# SCH_Arduino__V1_2023-10-04.net
KiCad netlist of a schematic drawn in EasyEDA
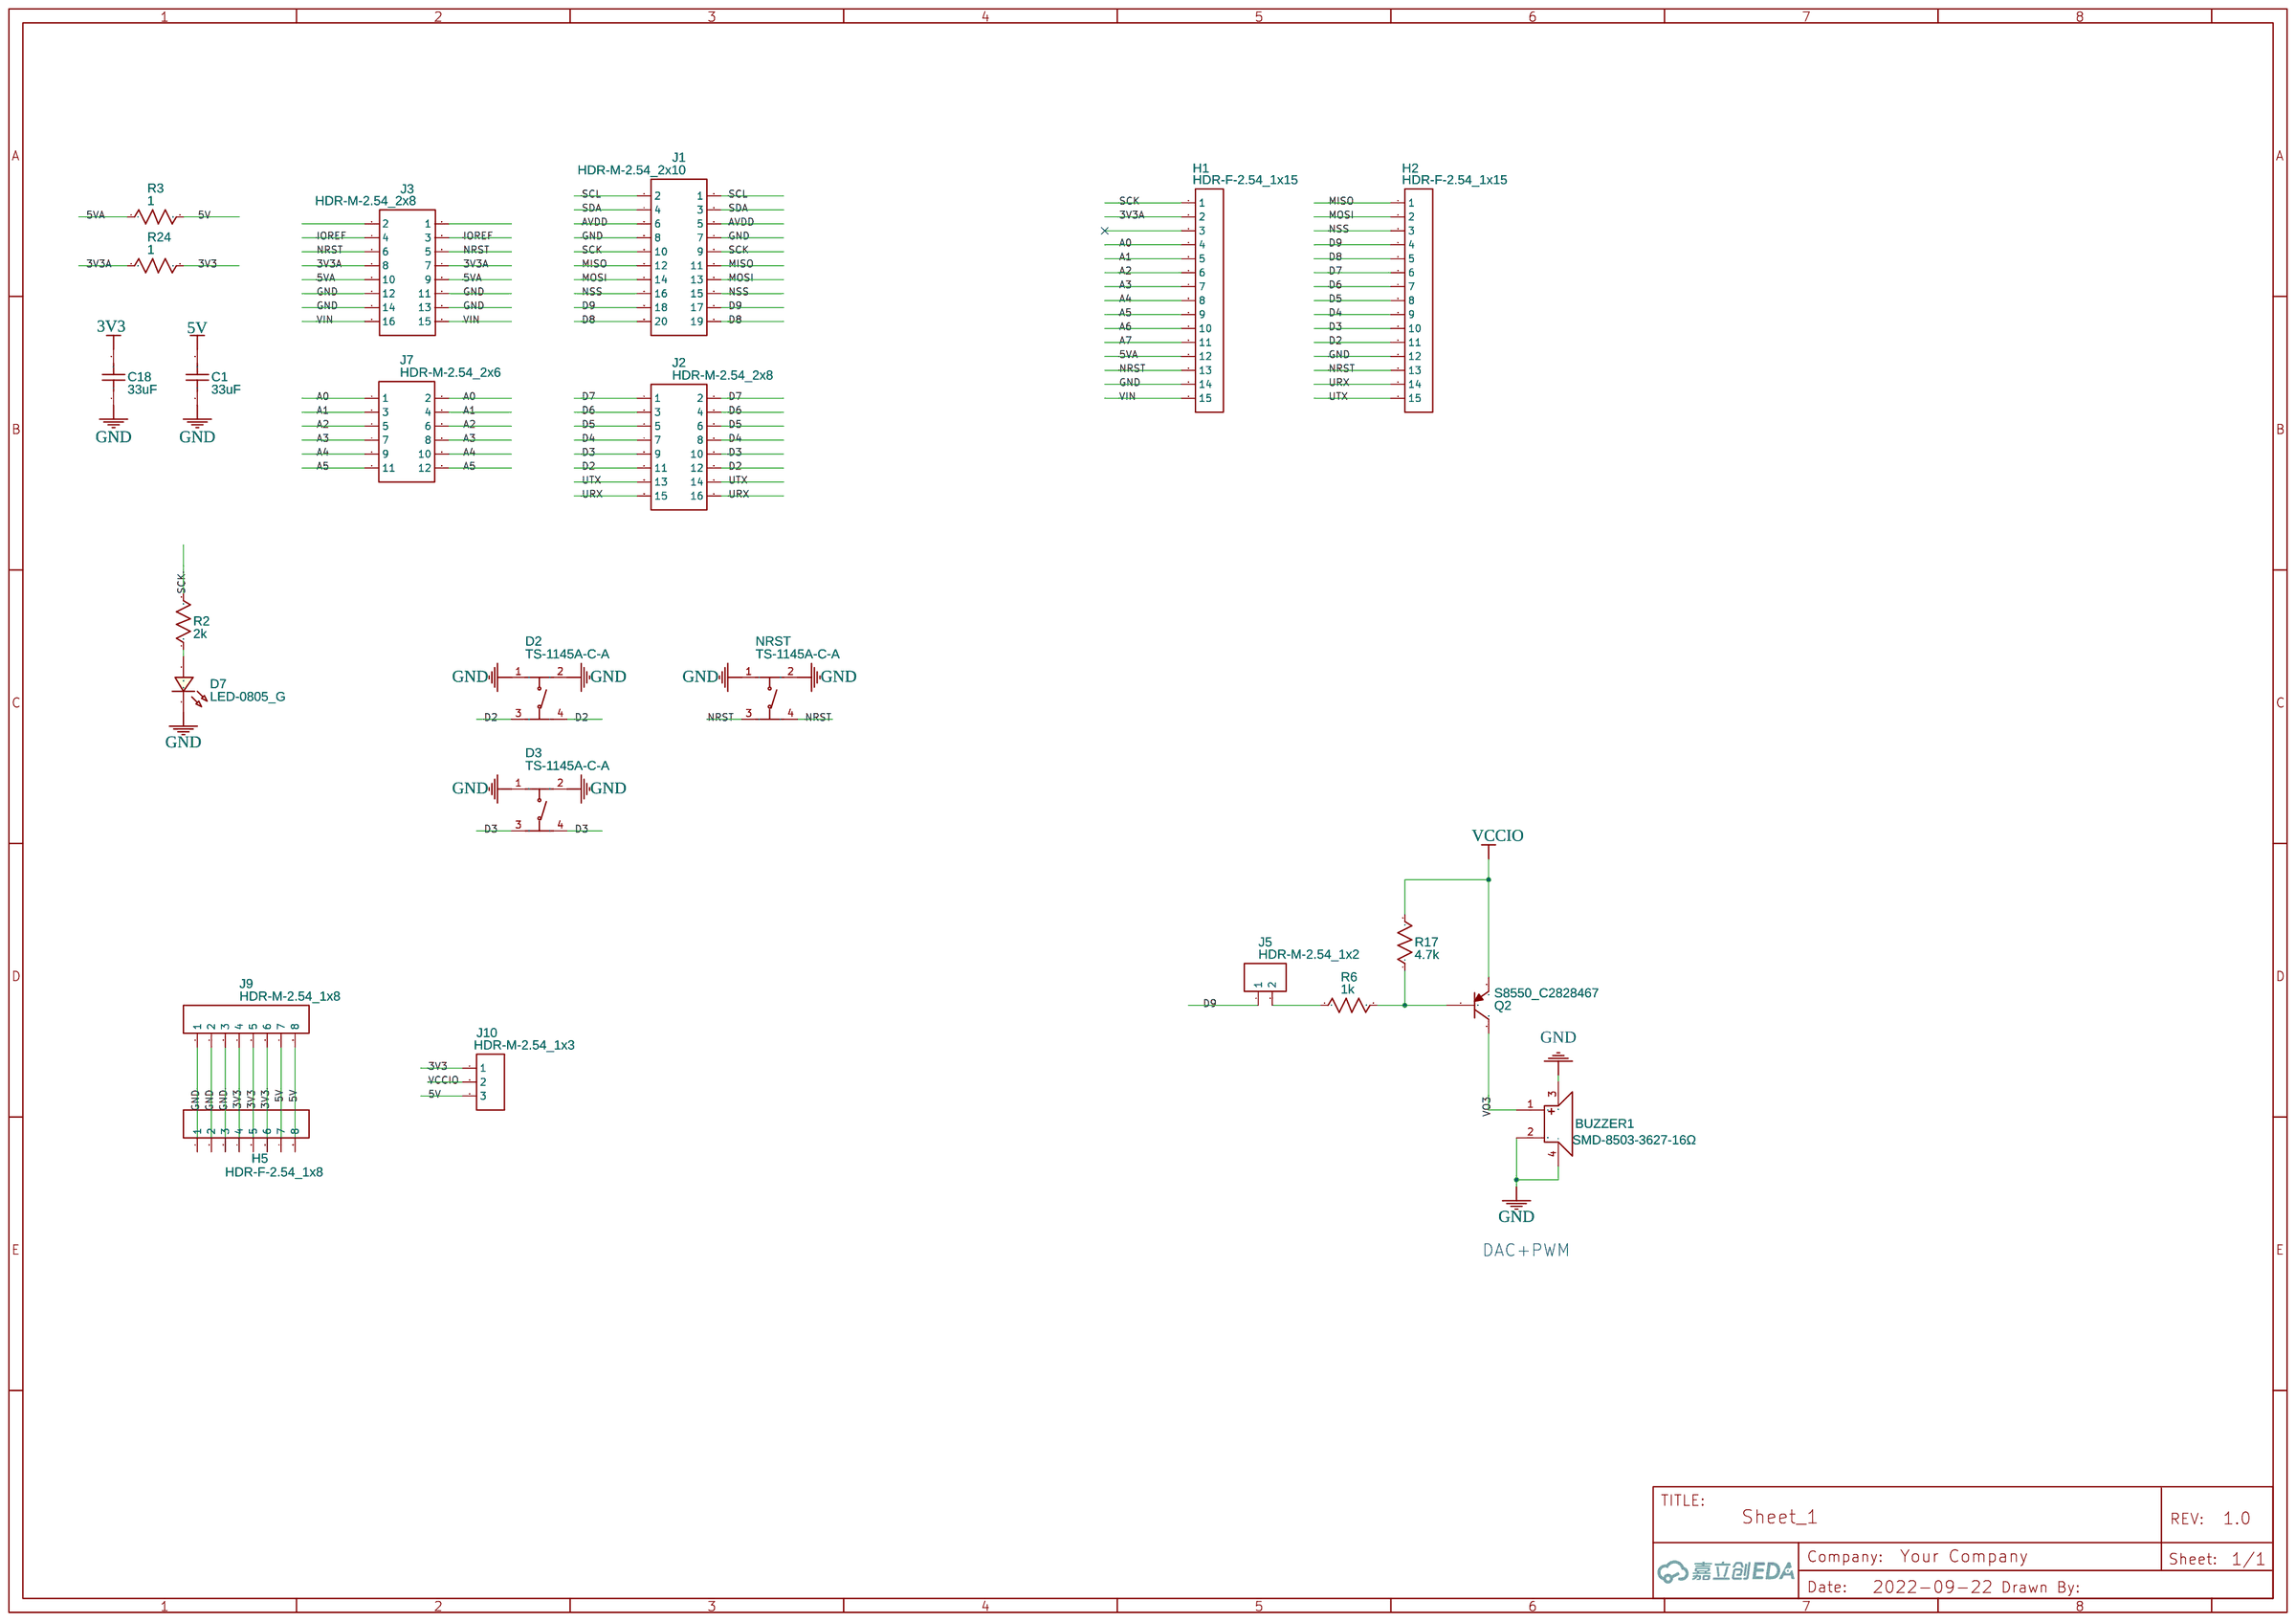
[diagram p0: 连接器]
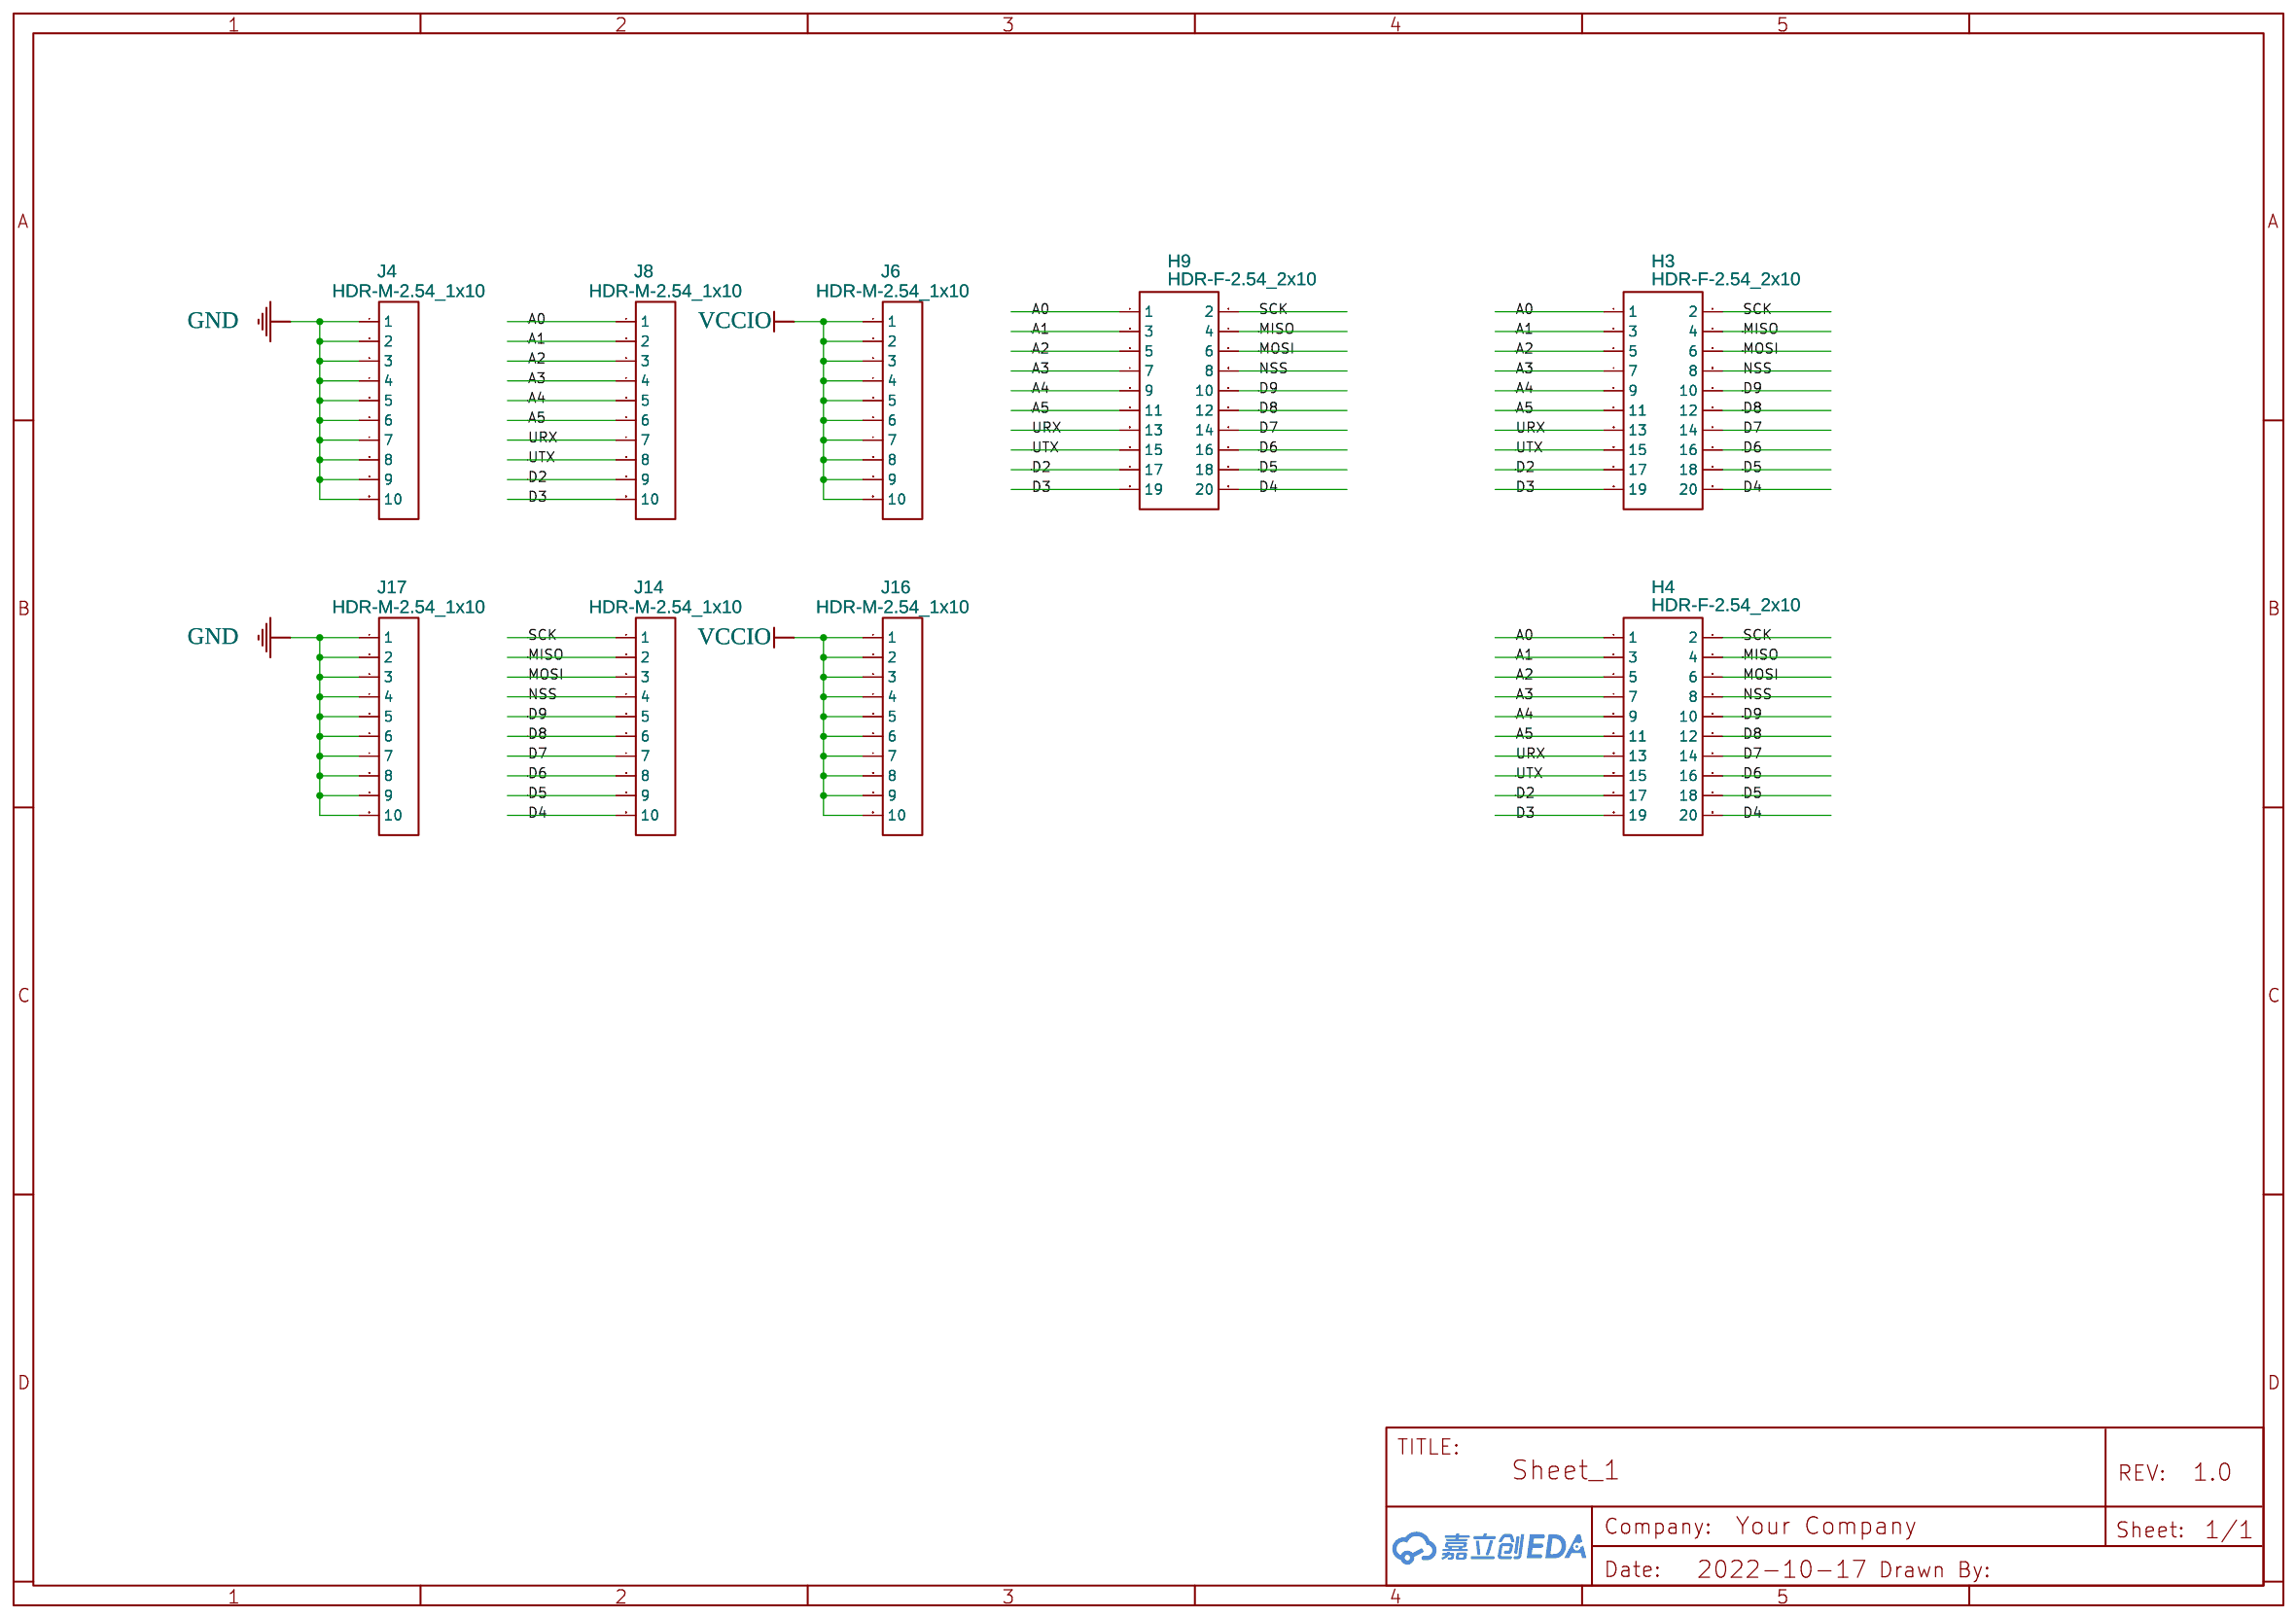
[diagram p1: 连接器扩展]

(export (version "E")
  (design (tool "Eeschema 10.0.6"))
  (components
    (comp (ref "BUZZER1")
      (value "SMD-8503-3627-16Ω")
      (fields (field (name "BOM_Supplier Part") "C2685545"))
      (libsource (lib "") (part "SMD-8503-3627-16Ω"))
    )
    (comp (ref "C1")
      (value "33uF")
      (fields
        (field (name "BOM_Manufacturer Part") "C3225X5R0J336MT0A0N")
        (field (name "BOM_Supplier Part") "C695362")
      )
      (libsource (lib "") (part "C3225X5R0J336MT0A0N"))
    )
    (comp (ref "C18")
      (value "33uF")
      (fields
        (field (name "BOM_Manufacturer Part") "C3225X5R0J336MT0A0N")
        (field (name "BOM_Supplier Part") "C695362")
      )
      (libsource (lib "") (part "C3225X5R0J336MT0A0N"))
    )
    (comp (ref "D2")
      (value "TS-1145A-C-A")
      (fields (field (name "BOM_Supplier Part") "C318903"))
      (libsource (lib "") (part "TS-1145A-C-A_1"))
    )
    (comp (ref "D3")
      (value "TS-1145A-C-A")
      (fields (field (name "BOM_Supplier Part") "C318903"))
      (libsource (lib "") (part "TS-1145A-C-A_1"))
    )
    (comp (ref "D7")
      (value "LED-0805_G")
      (fields (field (name "BOM_Manufacturer Part") "NCD0805G1") (field (name "BOM_Supplier Part") "C84260"))
      (libsource (lib "") (part "LED-0805_G"))
    )
    (comp (ref "H1")
      (value "HDR-F-2.54_1x15")
      (fields (field (name "BOM_Supplier Part") "C124408"))
      (libsource (lib "") (part "HDR-F-2.54_1x15"))
    )
    (comp (ref "H2")
      (value "HDR-F-2.54_1x15")
      (fields (field (name "BOM_Supplier Part") "C124408"))
      (libsource (lib "") (part "HDR-F-2.54_1x15"))
    )
    (comp (ref "H5")
      (value "HDR-F-2.54_1x8")
      (fields (field (name "BOM_Supplier Part") "C225505"))
      (libsource (lib "") (part "HDR-F-2.54_1x8"))
    )
    (comp (ref "J1")
      (value "HDR-M-2.54_2x10")
      (fields (field (name "BOM_Supplier Part") "C124359"))
      (libsource (lib "") (part "HDR-M-2.54_2x10"))
    )
    (comp (ref "J2")
      (value "HDR-M-2.54_2x8")
      (fields (field (name "BOM_Supplier Part") "C68234"))
      (libsource (lib "") (part "HDR-M-2.54_2x8_1"))
    )
    (comp (ref "J3")
      (value "HDR-M-2.54_2x8")
      (fields (field (name "BOM_Supplier Part") "C68234"))
      (libsource (lib "") (part "HDR-M-2.54_2x8"))
    )
    (comp (ref "J5")
      (value "HDR-M-2.54_1x2")
      (fields (field (name "BOM_Supplier Part") "C124375"))
      (libsource (lib "") (part "HDR-M-2.54_1x2"))
    )
    (comp (ref "J7")
      (value "HDR-M-2.54_2x6")
      (fields (field (name "BOM_Supplier Part") "C124388"))
      (libsource (lib "") (part "HDR-M-2.54_2x6"))
    )
    (comp (ref "J9")
      (value "HDR-M-2.54_1x8")
      (fields (field (name "BOM_Supplier Part") "C190820"))
      (libsource (lib "") (part "HDR-M-2.54_1x8"))
    )
    (comp (ref "J10")
      (value "HDR-M-2.54_1x3")
      (fields (field (name "BOM_Supplier Part") "C180248"))
      (libsource (lib "") (part "HDR-M-2.54_1x3"))
    )
    (comp (ref "NRST")
      (value "TS-1145A-C-A")
      (fields (field (name "BOM_Supplier Part") "C318903"))
      (libsource (lib "") (part "TS-1145A-C-A"))
    )
    (comp (ref "Q2")
      (value "S8550_C2828467")
      (fields (field (name "BOM_Manufacturer Part") "S8550") (field (name "BOM_Supplier Part") "C2828467"))
      (libsource (lib "") (part "S8550_C2828467"))
    )
    (comp (ref "R2")
      (value "2k")
      (fields
        (field (name "BOM_Manufacturer Part") "TC0525F1001T5E")
        (field (name "BOM_Supplier Part") "C75781")
      )
      (libsource (lib "") (part "R_0805_US"))
    )
    (comp (ref "R3") (value "1") (libsource (lib "") (part "R_0805_US_1")))
    (comp (ref "R6") (value "1k") (libsource (lib "") (part "R_0805_US_1")))
    (comp (ref "R17") (value "4.7k") (libsource (lib "") (part "R_0805_US")))
    (comp (ref "R24") (value "1") (libsource (lib "") (part "R_0805_US_1")))
    (comp (ref "H3")
      (value "HDR-F-2.54_2x10")
      (fields (field (name "BOM_Supplier Part") "C30867"))
      (libsource (lib "") (part "HDR-F-2.54_2x10"))
    )
    (comp (ref "H4")
      (value "HDR-F-2.54_2x10")
      (fields (field (name "BOM_Supplier Part") "C30867"))
      (libsource (lib "") (part "HDR-F-2.54_2x10"))
    )
    (comp (ref "H9")
      (value "HDR-F-2.54_2x10")
      (fields (field (name "BOM_Supplier Part") "C30867"))
      (libsource (lib "") (part "HDR-F-2.54_2x10"))
    )
    (comp (ref "J4")
      (value "HDR-M-2.54_1x10")
      (fields (field (name "BOM_Supplier Part") "C57369"))
      (libsource (lib "") (part "HDR-M-2.54_1x10"))
    )
    (comp (ref "J6")
      (value "HDR-M-2.54_1x10")
      (fields (field (name "BOM_Supplier Part") "C57369"))
      (libsource (lib "") (part "HDR-M-2.54_1x10"))
    )
    (comp (ref "J8")
      (value "HDR-M-2.54_1x10")
      (fields (field (name "BOM_Supplier Part") "C57369"))
      (libsource (lib "") (part "HDR-M-2.54_1x10"))
    )
    (comp (ref "J14")
      (value "HDR-M-2.54_1x10")
      (fields (field (name "BOM_Supplier Part") "C57369"))
      (libsource (lib "") (part "HDR-M-2.54_1x10"))
    )
    (comp (ref "J16")
      (value "HDR-M-2.54_1x10")
      (fields (field (name "BOM_Supplier Part") "C57369"))
      (libsource (lib "") (part "HDR-M-2.54_1x10"))
    )
    (comp (ref "J17")
      (value "HDR-M-2.54_1x10")
      (fields (field (name "BOM_Supplier Part") "C57369"))
      (libsource (lib "") (part "HDR-M-2.54_1x10"))
    )
  )
  (nets
    (net (code "1") (name "3V3") (class "Default")
      (node (ref "C18") (pin "2") (pinfunction "2_2") (pintype "unspecified"))
      (node (ref "H5") (pin "4") (pinfunction "4_4") (pintype "unspecified"))
      (node (ref "H5") (pin "5") (pinfunction "5_5") (pintype "unspecified"))
      (node (ref "H5") (pin "6") (pinfunction "6_6") (pintype "unspecified"))
      (node (ref "J10") (pin "1") (pinfunction "1_1") (pintype "input"))
      (node (ref "J9") (pin "4") (pinfunction "4_4") (pintype "unspecified"))
      (node (ref "J9") (pin "5") (pinfunction "5_5") (pintype "unspecified"))
      (node (ref "J9") (pin "6") (pinfunction "6_6") (pintype "unspecified"))
      (node (ref "R24") (pin "2") (pinfunction "2_2") (pintype "unspecified"))
    )
    (net (code "2") (name "3V3A") (class "Default")
      (node (ref "H1") (pin "2") (pinfunction "2_2") (pintype "unspecified"))
      (node (ref "J3") (pin "7") (pinfunction "7_7") (pintype "input"))
      (node (ref "J3") (pin "8") (pinfunction "8_8") (pintype "input"))
      (node (ref "R24") (pin "1") (pinfunction "1_1") (pintype "unspecified"))
    )
    (net (code "3") (name "5V") (class "Default")
      (node (ref "C1") (pin "2") (pinfunction "2_2") (pintype "unspecified"))
      (node (ref "H5") (pin "7") (pinfunction "7_7") (pintype "unspecified"))
      (node (ref "H5") (pin "8") (pinfunction "8_8") (pintype "unspecified"))
      (node (ref "J10") (pin "3") (pinfunction "3_3") (pintype "input"))
      (node (ref "J9") (pin "7") (pinfunction "7_7") (pintype "unspecified"))
      (node (ref "J9") (pin "8") (pinfunction "8_8") (pintype "unspecified"))
      (node (ref "R3") (pin "2") (pinfunction "2_2") (pintype "unspecified"))
    )
    (net (code "4") (name "5VA") (class "Default")
      (node (ref "H1") (pin "12") (pinfunction "12_12") (pintype "unspecified"))
      (node (ref "J3") (pin "10") (pinfunction "10_10") (pintype "input"))
      (node (ref "J3") (pin "9") (pinfunction "9_9") (pintype "input"))
      (node (ref "R3") (pin "1") (pinfunction "1_1") (pintype "unspecified"))
    )
    (net (code "5") (name "A0") (class "Default")
      (node (ref "H1") (pin "4") (pinfunction "4_4") (pintype "unspecified"))
      (node (ref "H3") (pin "1") (pinfunction "1_1") (pintype "input"))
      (node (ref "H4") (pin "1") (pinfunction "1_1") (pintype "input"))
      (node (ref "H9") (pin "1") (pinfunction "1_1") (pintype "input"))
      (node (ref "J7") (pin "1") (pinfunction "1_1") (pintype "unspecified"))
      (node (ref "J7") (pin "2") (pinfunction "2_2") (pintype "unspecified"))
      (node (ref "J8") (pin "1") (pinfunction "1_1") (pintype "unspecified"))
    )
    (net (code "6") (name "A1") (class "Default")
      (node (ref "H1") (pin "5") (pinfunction "5_5") (pintype "unspecified"))
      (node (ref "H3") (pin "3") (pinfunction "3_3") (pintype "input"))
      (node (ref "H4") (pin "3") (pinfunction "3_3") (pintype "input"))
      (node (ref "H9") (pin "3") (pinfunction "3_3") (pintype "input"))
      (node (ref "J7") (pin "3") (pinfunction "3_3") (pintype "unspecified"))
      (node (ref "J7") (pin "4") (pinfunction "4_4") (pintype "unspecified"))
      (node (ref "J8") (pin "2") (pinfunction "2_2") (pintype "unspecified"))
    )
    (net (code "7") (name "A2") (class "Default")
      (node (ref "H1") (pin "6") (pinfunction "6_6") (pintype "unspecified"))
      (node (ref "H3") (pin "5") (pinfunction "5_5") (pintype "input"))
      (node (ref "H4") (pin "5") (pinfunction "5_5") (pintype "input"))
      (node (ref "H9") (pin "5") (pinfunction "5_5") (pintype "input"))
      (node (ref "J7") (pin "5") (pinfunction "5_5") (pintype "unspecified"))
      (node (ref "J7") (pin "6") (pinfunction "6_6") (pintype "unspecified"))
      (node (ref "J8") (pin "3") (pinfunction "3_3") (pintype "unspecified"))
    )
    (net (code "8") (name "A3") (class "Default")
      (node (ref "H1") (pin "7") (pinfunction "7_7") (pintype "unspecified"))
      (node (ref "H3") (pin "7") (pinfunction "7_7") (pintype "input"))
      (node (ref "H4") (pin "7") (pinfunction "7_7") (pintype "input"))
      (node (ref "H9") (pin "7") (pinfunction "7_7") (pintype "input"))
      (node (ref "J7") (pin "7") (pinfunction "7_7") (pintype "unspecified"))
      (node (ref "J7") (pin "8") (pinfunction "8_8") (pintype "unspecified"))
      (node (ref "J8") (pin "4") (pinfunction "4_4") (pintype "unspecified"))
    )
    (net (code "9") (name "A4") (class "Default")
      (node (ref "H1") (pin "8") (pinfunction "8_8") (pintype "unspecified"))
      (node (ref "H3") (pin "9") (pinfunction "9_9") (pintype "input"))
      (node (ref "H4") (pin "9") (pinfunction "9_9") (pintype "input"))
      (node (ref "H9") (pin "9") (pinfunction "9_9") (pintype "input"))
      (node (ref "J7") (pin "10") (pinfunction "10_10") (pintype "unspecified"))
      (node (ref "J7") (pin "9") (pinfunction "9_9") (pintype "unspecified"))
      (node (ref "J8") (pin "5") (pinfunction "5_5") (pintype "unspecified"))
    )
    (net (code "10") (name "A5") (class "Default")
      (node (ref "H1") (pin "9") (pinfunction "9_9") (pintype "unspecified"))
      (node (ref "H3") (pin "11") (pinfunction "11_11") (pintype "input"))
      (node (ref "H4") (pin "11") (pinfunction "11_11") (pintype "input"))
      (node (ref "H9") (pin "11") (pinfunction "11_11") (pintype "input"))
      (node (ref "J7") (pin "11") (pinfunction "11_11") (pintype "unspecified"))
      (node (ref "J7") (pin "12") (pinfunction "12_12") (pintype "unspecified"))
      (node (ref "J8") (pin "6") (pinfunction "6_6") (pintype "unspecified"))
    )
    (net (code "11") (name "A6") (class "Default")
      (node (ref "H1") (pin "10") (pinfunction "10_10") (pintype "unspecified"))
    )
    (net (code "12") (name "A7") (class "Default")
      (node (ref "H1") (pin "11") (pinfunction "11_11") (pintype "unspecified"))
    )
    (net (code "13") (name "AVDD") (class "Default")
      (node (ref "J1") (pin "5") (pinfunction "5_5") (pintype "unspecified"))
      (node (ref "J1") (pin "6") (pinfunction "6_6") (pintype "unspecified"))
    )
    (net (code "14") (name "D2") (class "Default")
      (node (ref "D2") (pin "3") (pinfunction "3_3") (pintype "unspecified"))
      (node (ref "D2") (pin "4") (pinfunction "4_4") (pintype "unspecified"))
      (node (ref "H2") (pin "11") (pinfunction "11_11") (pintype "unspecified"))
      (node (ref "H3") (pin "17") (pinfunction "17_17") (pintype "input"))
      (node (ref "H4") (pin "17") (pinfunction "17_17") (pintype "input"))
      (node (ref "H9") (pin "17") (pinfunction "17_17") (pintype "input"))
      (node (ref "J2") (pin "11") (pinfunction "11_11") (pintype "input"))
      (node (ref "J2") (pin "12") (pinfunction "12_12") (pintype "input"))
      (node (ref "J8") (pin "9") (pinfunction "9_9") (pintype "unspecified"))
    )
    (net (code "15") (name "D3") (class "Default")
      (node (ref "D3") (pin "3") (pinfunction "3_3") (pintype "unspecified"))
      (node (ref "D3") (pin "4") (pinfunction "4_4") (pintype "unspecified"))
      (node (ref "H2") (pin "10") (pinfunction "10_10") (pintype "unspecified"))
      (node (ref "H3") (pin "19") (pinfunction "19_19") (pintype "input"))
      (node (ref "H4") (pin "19") (pinfunction "19_19") (pintype "input"))
      (node (ref "H9") (pin "19") (pinfunction "19_19") (pintype "input"))
      (node (ref "J2") (pin "10") (pinfunction "10_10") (pintype "input"))
      (node (ref "J2") (pin "9") (pinfunction "9_9") (pintype "input"))
      (node (ref "J8") (pin "10") (pinfunction "10_10") (pintype "unspecified"))
    )
    (net (code "16") (name "D4") (class "Default")
      (node (ref "H2") (pin "9") (pinfunction "9_9") (pintype "unspecified"))
      (node (ref "H3") (pin "20") (pinfunction "20_20") (pintype "input"))
      (node (ref "H4") (pin "20") (pinfunction "20_20") (pintype "input"))
      (node (ref "H9") (pin "20") (pinfunction "20_20") (pintype "input"))
      (node (ref "J14") (pin "10") (pinfunction "10_10") (pintype "unspecified"))
      (node (ref "J2") (pin "7") (pinfunction "7_7") (pintype "input"))
      (node (ref "J2") (pin "8") (pinfunction "8_8") (pintype "input"))
    )
    (net (code "17") (name "D5") (class "Default")
      (node (ref "H2") (pin "8") (pinfunction "8_8") (pintype "unspecified"))
      (node (ref "H3") (pin "18") (pinfunction "18_18") (pintype "input"))
      (node (ref "H4") (pin "18") (pinfunction "18_18") (pintype "input"))
      (node (ref "H9") (pin "18") (pinfunction "18_18") (pintype "input"))
      (node (ref "J14") (pin "9") (pinfunction "9_9") (pintype "unspecified"))
      (node (ref "J2") (pin "5") (pinfunction "5_5") (pintype "input"))
      (node (ref "J2") (pin "6") (pinfunction "6_6") (pintype "input"))
    )
    (net (code "18") (name "D6") (class "Default")
      (node (ref "H2") (pin "7") (pinfunction "7_7") (pintype "unspecified"))
      (node (ref "H3") (pin "16") (pinfunction "16_16") (pintype "input"))
      (node (ref "H4") (pin "16") (pinfunction "16_16") (pintype "input"))
      (node (ref "H9") (pin "16") (pinfunction "16_16") (pintype "input"))
      (node (ref "J14") (pin "8") (pinfunction "8_8") (pintype "unspecified"))
      (node (ref "J2") (pin "3") (pinfunction "3_3") (pintype "input"))
      (node (ref "J2") (pin "4") (pinfunction "4_4") (pintype "input"))
    )
    (net (code "19") (name "D7") (class "Default")
      (node (ref "H2") (pin "6") (pinfunction "6_6") (pintype "unspecified"))
      (node (ref "H3") (pin "14") (pinfunction "14_14") (pintype "input"))
      (node (ref "H4") (pin "14") (pinfunction "14_14") (pintype "input"))
      (node (ref "H9") (pin "14") (pinfunction "14_14") (pintype "input"))
      (node (ref "J14") (pin "7") (pinfunction "7_7") (pintype "unspecified"))
      (node (ref "J2") (pin "1") (pinfunction "1_1") (pintype "input"))
      (node (ref "J2") (pin "2") (pinfunction "2_2") (pintype "input"))
    )
    (net (code "20") (name "D8") (class "Default")
      (node (ref "H2") (pin "5") (pinfunction "5_5") (pintype "unspecified"))
      (node (ref "H3") (pin "12") (pinfunction "12_12") (pintype "input"))
      (node (ref "H4") (pin "12") (pinfunction "12_12") (pintype "input"))
      (node (ref "H9") (pin "12") (pinfunction "12_12") (pintype "input"))
      (node (ref "J1") (pin "19") (pinfunction "19_19") (pintype "unspecified"))
      (node (ref "J1") (pin "20") (pinfunction "20_20") (pintype "unspecified"))
      (node (ref "J14") (pin "6") (pinfunction "6_6") (pintype "unspecified"))
    )
    (net (code "21") (name "D9") (class "Default")
      (node (ref "H2") (pin "4") (pinfunction "4_4") (pintype "unspecified"))
      (node (ref "H3") (pin "10") (pinfunction "10_10") (pintype "input"))
      (node (ref "H4") (pin "10") (pinfunction "10_10") (pintype "input"))
      (node (ref "H9") (pin "10") (pinfunction "10_10") (pintype "input"))
      (node (ref "J1") (pin "17") (pinfunction "17_17") (pintype "unspecified"))
      (node (ref "J1") (pin "18") (pinfunction "18_18") (pintype "unspecified"))
      (node (ref "J14") (pin "5") (pinfunction "5_5") (pintype "unspecified"))
      (node (ref "J5") (pin "1") (pinfunction "1_1") (pintype "unspecified"))
    )
    (net (code "22") (name "GND") (class "Default")
      (node (ref "BUZZER1") (pin "2") (pinfunction "2_2") (pintype "unspecified"))
      (node (ref "BUZZER1") (pin "3") (pinfunction "3_3") (pintype "unspecified"))
      (node (ref "BUZZER1") (pin "4") (pinfunction "4_4") (pintype "unspecified"))
      (node (ref "C1") (pin "1") (pinfunction "1_1") (pintype "unspecified"))
      (node (ref "C18") (pin "1") (pinfunction "1_1") (pintype "unspecified"))
      (node (ref "D2") (pin "1") (pinfunction "1_1") (pintype "unspecified"))
      (node (ref "D2") (pin "2") (pinfunction "2_2") (pintype "unspecified"))
      (node (ref "D3") (pin "1") (pinfunction "1_1") (pintype "unspecified"))
      (node (ref "D3") (pin "2") (pinfunction "2_2") (pintype "unspecified"))
      (node (ref "D7") (pin "2") (pinfunction "2_2") (pintype "unspecified"))
      (node (ref "H1") (pin "14") (pinfunction "14_14") (pintype "unspecified"))
      (node (ref "H2") (pin "12") (pinfunction "12_12") (pintype "unspecified"))
      (node (ref "H5") (pin "1") (pinfunction "1_1") (pintype "unspecified"))
      (node (ref "H5") (pin "2") (pinfunction "2_2") (pintype "unspecified"))
      (node (ref "H5") (pin "3") (pinfunction "3_3") (pintype "unspecified"))
      (node (ref "J1") (pin "7") (pinfunction "7_7") (pintype "unspecified"))
      (node (ref "J1") (pin "8") (pinfunction "8_8") (pintype "unspecified"))
      (node (ref "J17") (pin "1") (pinfunction "1_1") (pintype "unspecified"))
      (node (ref "J17") (pin "10") (pinfunction "10_10") (pintype "unspecified"))
      (node (ref "J17") (pin "2") (pinfunction "2_2") (pintype "unspecified"))
      (node (ref "J17") (pin "3") (pinfunction "3_3") (pintype "unspecified"))
      (node (ref "J17") (pin "4") (pinfunction "4_4") (pintype "unspecified"))
      (node (ref "J17") (pin "5") (pinfunction "5_5") (pintype "unspecified"))
      (node (ref "J17") (pin "6") (pinfunction "6_6") (pintype "unspecified"))
      (node (ref "J17") (pin "7") (pinfunction "7_7") (pintype "unspecified"))
      (node (ref "J17") (pin "8") (pinfunction "8_8") (pintype "unspecified"))
      (node (ref "J17") (pin "9") (pinfunction "9_9") (pintype "unspecified"))
      (node (ref "J3") (pin "11") (pinfunction "11_11") (pintype "input"))
      (node (ref "J3") (pin "12") (pinfunction "12_12") (pintype "input"))
      (node (ref "J3") (pin "13") (pinfunction "13_13") (pintype "input"))
      (node (ref "J3") (pin "14") (pinfunction "14_14") (pintype "input"))
      (node (ref "J4") (pin "1") (pinfunction "1_1") (pintype "unspecified"))
      (node (ref "J4") (pin "10") (pinfunction "10_10") (pintype "unspecified"))
      (node (ref "J4") (pin "2") (pinfunction "2_2") (pintype "unspecified"))
      (node (ref "J4") (pin "3") (pinfunction "3_3") (pintype "unspecified"))
      (node (ref "J4") (pin "4") (pinfunction "4_4") (pintype "unspecified"))
      (node (ref "J4") (pin "5") (pinfunction "5_5") (pintype "unspecified"))
      (node (ref "J4") (pin "6") (pinfunction "6_6") (pintype "unspecified"))
      (node (ref "J4") (pin "7") (pinfunction "7_7") (pintype "unspecified"))
      (node (ref "J4") (pin "8") (pinfunction "8_8") (pintype "unspecified"))
      (node (ref "J4") (pin "9") (pinfunction "9_9") (pintype "unspecified"))
      (node (ref "J9") (pin "1") (pinfunction "1_1") (pintype "unspecified"))
      (node (ref "J9") (pin "2") (pinfunction "2_2") (pintype "unspecified"))
      (node (ref "J9") (pin "3") (pinfunction "3_3") (pintype "unspecified"))
      (node (ref "NRST") (pin "1") (pinfunction "1_1") (pintype "unspecified"))
      (node (ref "NRST") (pin "2") (pinfunction "2_2") (pintype "unspecified"))
    )
    (net (code "23") (name "IOREF") (class "Default")
      (node (ref "J3") (pin "3") (pinfunction "3_3") (pintype "input"))
      (node (ref "J3") (pin "4") (pinfunction "4_4") (pintype "input"))
    )
    (net (code "24") (name "MISO") (class "Default")
      (node (ref "H2") (pin "1") (pinfunction "1_1") (pintype "unspecified"))
      (node (ref "H3") (pin "4") (pinfunction "4_4") (pintype "input"))
      (node (ref "H4") (pin "4") (pinfunction "4_4") (pintype "input"))
      (node (ref "H9") (pin "4") (pinfunction "4_4") (pintype "input"))
      (node (ref "J1") (pin "11") (pinfunction "11_11") (pintype "unspecified"))
      (node (ref "J1") (pin "12") (pinfunction "12_12") (pintype "unspecified"))
      (node (ref "J14") (pin "2") (pinfunction "2_2") (pintype "unspecified"))
    )
    (net (code "25") (name "MOSI") (class "Default")
      (node (ref "H2") (pin "2") (pinfunction "2_2") (pintype "unspecified"))
      (node (ref "H3") (pin "6") (pinfunction "6_6") (pintype "input"))
      (node (ref "H4") (pin "6") (pinfunction "6_6") (pintype "input"))
      (node (ref "H9") (pin "6") (pinfunction "6_6") (pintype "input"))
      (node (ref "J1") (pin "13") (pinfunction "13_13") (pintype "unspecified"))
      (node (ref "J1") (pin "14") (pinfunction "14_14") (pintype "unspecified"))
      (node (ref "J14") (pin "3") (pinfunction "3_3") (pintype "unspecified"))
    )
    (net (code "26") (name "NRST") (class "Default")
      (node (ref "H1") (pin "13") (pinfunction "13_13") (pintype "unspecified"))
      (node (ref "H2") (pin "13") (pinfunction "13_13") (pintype "unspecified"))
      (node (ref "J3") (pin "5") (pinfunction "5_5") (pintype "input"))
      (node (ref "J3") (pin "6") (pinfunction "6_6") (pintype "input"))
      (node (ref "NRST") (pin "3") (pinfunction "3_3") (pintype "unspecified"))
      (node (ref "NRST") (pin "4") (pinfunction "4_4") (pintype "unspecified"))
    )
    (net (code "27") (name "NSS") (class "Default")
      (node (ref "H2") (pin "3") (pinfunction "3_3") (pintype "unspecified"))
      (node (ref "H3") (pin "8") (pinfunction "8_8") (pintype "input"))
      (node (ref "H4") (pin "8") (pinfunction "8_8") (pintype "input"))
      (node (ref "H9") (pin "8") (pinfunction "8_8") (pintype "input"))
      (node (ref "J1") (pin "15") (pinfunction "15_15") (pintype "unspecified"))
      (node (ref "J1") (pin "16") (pinfunction "16_16") (pintype "unspecified"))
      (node (ref "J14") (pin "4") (pinfunction "4_4") (pintype "unspecified"))
    )
    (net (code "28") (name "Net-(D7-Pad1)") (class "Default")
      (node (ref "D7") (pin "1") (pinfunction "1_1") (pintype "unspecified"))
      (node (ref "R2") (pin "1") (pinfunction "1_1") (pintype "unspecified"))
    )
    (net (code "29") (name "Net-(J5-Pad2)") (class "Default")
      (node (ref "J5") (pin "2") (pinfunction "2_2") (pintype "unspecified"))
      (node (ref "R6") (pin "1") (pinfunction "1_1") (pintype "unspecified"))
    )
    (net (code "30") (name "Net-(Q2-B)") (class "Default")
      (node (ref "Q2") (pin "1") (pinfunction "B_1") (pintype "unspecified"))
      (node (ref "R17") (pin "1") (pinfunction "1_1") (pintype "unspecified"))
      (node (ref "R6") (pin "2") (pinfunction "2_2") (pintype "unspecified"))
    )
    (net (code "31") (name "SCK") (class "Default")
      (node (ref "H1") (pin "1") (pinfunction "1_1") (pintype "unspecified"))
      (node (ref "H3") (pin "2") (pinfunction "2_2") (pintype "input"))
      (node (ref "H4") (pin "2") (pinfunction "2_2") (pintype "input"))
      (node (ref "H9") (pin "2") (pinfunction "2_2") (pintype "input"))
      (node (ref "J1") (pin "10") (pinfunction "10_10") (pintype "unspecified"))
      (node (ref "J1") (pin "9") (pinfunction "9_9") (pintype "unspecified"))
      (node (ref "J14") (pin "1") (pinfunction "1_1") (pintype "unspecified"))
      (node (ref "R2") (pin "2") (pinfunction "2_2") (pintype "unspecified"))
    )
    (net (code "32") (name "SCL") (class "Default")
      (node (ref "J1") (pin "1") (pinfunction "1_1") (pintype "unspecified"))
      (node (ref "J1") (pin "2") (pinfunction "2_2") (pintype "unspecified"))
    )
    (net (code "33") (name "SDA") (class "Default")
      (node (ref "J1") (pin "3") (pinfunction "3_3") (pintype "unspecified"))
      (node (ref "J1") (pin "4") (pinfunction "4_4") (pintype "unspecified"))
    )
    (net (code "34") (name "URX") (class "Default")
      (node (ref "H2") (pin "14") (pinfunction "14_14") (pintype "unspecified"))
      (node (ref "H3") (pin "13") (pinfunction "13_13") (pintype "input"))
      (node (ref "H4") (pin "13") (pinfunction "13_13") (pintype "input"))
      (node (ref "H9") (pin "13") (pinfunction "13_13") (pintype "input"))
      (node (ref "J2") (pin "15") (pinfunction "15_15") (pintype "input"))
      (node (ref "J2") (pin "16") (pinfunction "16_16") (pintype "input"))
      (node (ref "J8") (pin "7") (pinfunction "7_7") (pintype "unspecified"))
    )
    (net (code "35") (name "UTX") (class "Default")
      (node (ref "H2") (pin "15") (pinfunction "15_15") (pintype "unspecified"))
      (node (ref "H3") (pin "15") (pinfunction "15_15") (pintype "input"))
      (node (ref "H4") (pin "15") (pinfunction "15_15") (pintype "input"))
      (node (ref "H9") (pin "15") (pinfunction "15_15") (pintype "input"))
      (node (ref "J2") (pin "13") (pinfunction "13_13") (pintype "input"))
      (node (ref "J2") (pin "14") (pinfunction "14_14") (pintype "input"))
      (node (ref "J8") (pin "8") (pinfunction "8_8") (pintype "unspecified"))
    )
    (net (code "36") (name "VCCIO") (class "Default")
      (node (ref "J10") (pin "2") (pinfunction "2_2") (pintype "input"))
      (node (ref "J16") (pin "1") (pinfunction "1_1") (pintype "unspecified"))
      (node (ref "J16") (pin "10") (pinfunction "10_10") (pintype "unspecified"))
      (node (ref "J16") (pin "2") (pinfunction "2_2") (pintype "unspecified"))
      (node (ref "J16") (pin "3") (pinfunction "3_3") (pintype "unspecified"))
      (node (ref "J16") (pin "4") (pinfunction "4_4") (pintype "unspecified"))
      (node (ref "J16") (pin "5") (pinfunction "5_5") (pintype "unspecified"))
      (node (ref "J16") (pin "6") (pinfunction "6_6") (pintype "unspecified"))
      (node (ref "J16") (pin "7") (pinfunction "7_7") (pintype "unspecified"))
      (node (ref "J16") (pin "8") (pinfunction "8_8") (pintype "unspecified"))
      (node (ref "J16") (pin "9") (pinfunction "9_9") (pintype "unspecified"))
      (node (ref "J6") (pin "1") (pinfunction "1_1") (pintype "unspecified"))
      (node (ref "J6") (pin "10") (pinfunction "10_10") (pintype "unspecified"))
      (node (ref "J6") (pin "2") (pinfunction "2_2") (pintype "unspecified"))
      (node (ref "J6") (pin "3") (pinfunction "3_3") (pintype "unspecified"))
      (node (ref "J6") (pin "4") (pinfunction "4_4") (pintype "unspecified"))
      (node (ref "J6") (pin "5") (pinfunction "5_5") (pintype "unspecified"))
      (node (ref "J6") (pin "6") (pinfunction "6_6") (pintype "unspecified"))
      (node (ref "J6") (pin "7") (pinfunction "7_7") (pintype "unspecified"))
      (node (ref "J6") (pin "8") (pinfunction "8_8") (pintype "unspecified"))
      (node (ref "J6") (pin "9") (pinfunction "9_9") (pintype "unspecified"))
      (node (ref "Q2") (pin "2") (pinfunction "E_2") (pintype "unspecified"))
      (node (ref "R17") (pin "2") (pinfunction "2_2") (pintype "unspecified"))
    )
    (net (code "37") (name "VIN") (class "Default")
      (node (ref "H1") (pin "15") (pinfunction "15_15") (pintype "unspecified"))
      (node (ref "J3") (pin "15") (pinfunction "15_15") (pintype "input"))
      (node (ref "J3") (pin "16") (pinfunction "16_16") (pintype "input"))
    )
    (net (code "38") (name "VO3") (class "Default")
      (node (ref "BUZZER1") (pin "1") (pinfunction "1_1") (pintype "unspecified"))
      (node (ref "Q2") (pin "3") (pinfunction "C_3") (pintype "unspecified"))
    )
    (net (code "39") (name "unconnected-(H1-Pad3)") (class "Default")
      (node (ref "H1") (pin "3") (pinfunction "3_3") (pintype "unspecified+no_connect"))
    )
    (net (code "40") (name "unconnected-(J3-Pad1)") (class "Default")
      (node (ref "J3") (pin "1") (pinfunction "1_1") (pintype "input"))
    )
    (net (code "41") (name "unconnected-(J3-Pad2)") (class "Default")
      (node (ref "J3") (pin "2") (pinfunction "2_2") (pintype "input"))
    )
  )
)
